# 26-TouchPad4P.net
KiCad netlist of a schematic drawn in Altium Designer
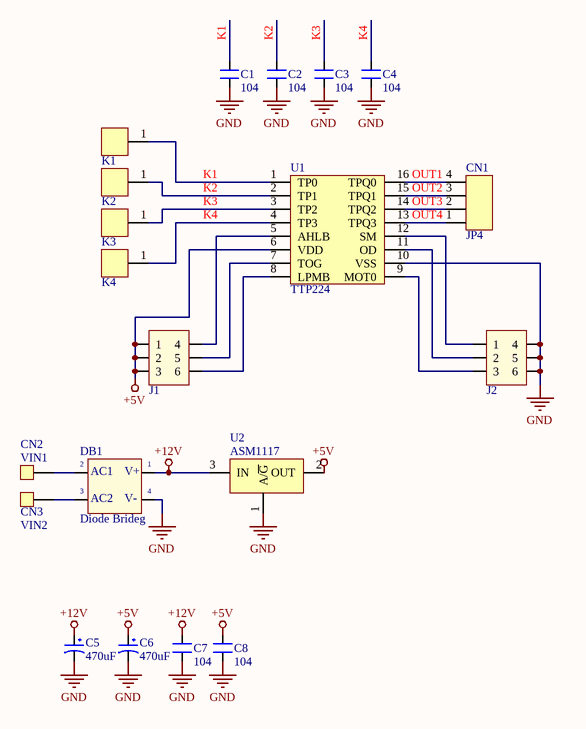
[diagram p0: 26-TouchPad4P.SchDoc]

(export (version "E")
  (design (tool "Eeschema 10.0.6"))
  (components
    (comp (ref "C1")
      (value "104")
      (footprint "C-0805")
      (fields (field (name "DESIGNED BY") "VanDungEvn"))
      (libsource (lib "syhaunguyen") (part "CN"))
    )
    (comp (ref "C2")
      (value "104")
      (footprint "C-0805")
      (fields (field (name "DESIGNED BY") "VanDungEvn"))
      (libsource (lib "syhaunguyen") (part "CN"))
    )
    (comp (ref "C3")
      (value "104")
      (footprint "C-0805")
      (fields (field (name "DESIGNED BY") "VanDungEvn"))
      (libsource (lib "syhaunguyen") (part "CN"))
    )
    (comp (ref "C4")
      (value "104")
      (footprint "C-0805")
      (fields (field (name "DESIGNED BY") "VanDungEvn"))
      (libsource (lib "syhaunguyen") (part "CN"))
    )
    (comp (ref "C5")
      (value "470uF")
      (footprint "C-ALU-D6.5")
      (description "Cap P  0,1uF < 22uF , 16 - 50V")
      (libsource (lib "PART") (part "CP1"))
    )
    (comp (ref "C6")
      (value "470uF")
      (footprint "C-ALU-D6.5")
      (description "Cap P  0,1uF < 22uF , 16 - 50V")
      (libsource (lib "PART") (part "CP1"))
    )
    (comp (ref "C7")
      (value "104")
      (footprint "C-0805")
      (fields (field (name "DESIGNED BY") "VanDungEvn"))
      (libsource (lib "syhaunguyen") (part "CN"))
    )
    (comp (ref "C8")
      (value "104")
      (footprint "C-0805")
      (fields (field (name "DESIGNED BY") "VanDungEvn"))
      (libsource (lib "syhaunguyen") (part "CN"))
    )
    (comp (ref "CN1") (value "JP4") (footprint "JP4") (libsource (lib "doAnTotNghiep2017Lib") (part "JP4")))
    (comp (ref "CN2")
      (value "VIN1")
      (footprint "M3")
      (libsource (lib "doAnTotNghiep2017Lib") (part "COCDONGM3"))
    )
    (comp (ref "CN3")
      (value "VIN2")
      (footprint "M3")
      (libsource (lib "doAnTotNghiep2017Lib") (part "COCDONGM3"))
    )
    (comp (ref "DB1")
      (value "Diode Brideg")
      (footprint "D-DB-1A-SMD")
      (description "Convert AC to DC voltage, 4 pin")
      (libsource (lib "PART") (part "DB"))
    )
    (comp (ref "J1")
      (value "Connector 3x2")
      (footprint "JP3x2")
      (libsource (lib "syhaunguyen") (part "JP3x2"))
    )
    (comp (ref "J2")
      (value "Connector 3x2")
      (footprint "JP3x2")
      (libsource (lib "syhaunguyen") (part "JP3x2"))
    )
    (comp (ref "K1") (value "SWCP") (footprint "SWCP") (libsource (lib "doAnTotNghiep2017Lib") (part "SWCP")))
    (comp (ref "K2") (value "SWCP") (footprint "SWCP") (libsource (lib "doAnTotNghiep2017Lib") (part "SWCP")))
    (comp (ref "K3") (value "SWCP") (footprint "SWCP") (libsource (lib "doAnTotNghiep2017Lib") (part "SWCP")))
    (comp (ref "K4") (value "SWCP") (footprint "SWCP") (libsource (lib "doAnTotNghiep2017Lib") (part "SWCP")))
    (comp (ref "U1")
      (value "TTP224")
      (footprint "SSOP-20")
      (libsource (lib "doAnTotNghiep2017Lib") (part "TTP224"))
    )
    (comp (ref "U2")
      (value "ASM1117")
      (footprint "TO-252")
      (libsource (lib "doAnTotNghiep2017Lib") (part "ASM1117"))
    )
  )
  (nets
    (net (code "1") (name "+5V") (class "Default")
      (node (ref "C6") (pin "1") (pinfunction "1_1") (pintype "passive"))
      (node (ref "C8") (pin "2") (pinfunction "2_2") (pintype "passive"))
      (node (ref "J1") (pin "1") (pinfunction "1_1") (pintype "passive"))
      (node (ref "J1") (pin "2") (pinfunction "2_2") (pintype "passive"))
      (node (ref "J1") (pin "3") (pinfunction "3_3") (pintype "passive"))
      (node (ref "U1") (pin "6") (pinfunction "VDD_6") (pintype "passive"))
      (node (ref "U2") (pin "2") (pinfunction "OUT_2") (pintype "passive"))
    )
    (net (code "2") (name "+12V") (class "Default")
      (node (ref "C5") (pin "1") (pinfunction "1_1") (pintype "passive"))
      (node (ref "C7") (pin "2") (pinfunction "2_2") (pintype "passive"))
      (node (ref "DB1") (pin "3") (pinfunction "AC2_3") (pintype "passive"))
      (node (ref "U2") (pin "3") (pinfunction "IN_3") (pintype "passive"))
    )
    (net (code "3") (name "/K1") (class "Default")
      (node (ref "C1") (pin "2") (pinfunction "2_2") (pintype "passive"))
      (node (ref "K1") (pin "1") (pintype "passive"))
      (node (ref "U1") (pin "1") (pinfunction "TP0_1") (pintype "passive"))
    )
    (net (code "4") (name "/K2") (class "Default")
      (node (ref "C2") (pin "2") (pinfunction "2_2") (pintype "passive"))
      (node (ref "K2") (pin "1") (pintype "passive"))
      (node (ref "U1") (pin "2") (pinfunction "TP1_2") (pintype "passive"))
    )
    (net (code "5") (name "/K3") (class "Default")
      (node (ref "C3") (pin "2") (pinfunction "2_2") (pintype "passive"))
      (node (ref "K3") (pin "1") (pintype "passive"))
      (node (ref "U1") (pin "3") (pinfunction "TP2_3") (pintype "passive"))
    )
    (net (code "6") (name "/K4") (class "Default")
      (node (ref "C4") (pin "2") (pinfunction "2_2") (pintype "passive"))
      (node (ref "K4") (pin "1") (pintype "passive"))
      (node (ref "U1") (pin "4") (pinfunction "TP3_4") (pintype "passive"))
    )
    (net (code "7") (name "/OUT1") (class "Default")
      (node (ref "CN1") (pin "4") (pintype "passive"))
      (node (ref "U1") (pin "16") (pinfunction "TPQ0_16") (pintype "passive"))
    )
    (net (code "8") (name "/OUT2") (class "Default")
      (node (ref "CN1") (pin "3") (pintype "passive"))
      (node (ref "U1") (pin "15") (pinfunction "TPQ1_15") (pintype "passive"))
    )
    (net (code "9") (name "/OUT3") (class "Default")
      (node (ref "CN1") (pin "2") (pintype "passive"))
      (node (ref "U1") (pin "14") (pinfunction "TPQ2_14") (pintype "passive"))
    )
    (net (code "10") (name "/OUT4") (class "Default")
      (node (ref "CN1") (pin "1") (pintype "passive"))
      (node (ref "U1") (pin "13") (pinfunction "TPQ3_13") (pintype "passive"))
    )
    (net (code "11") (name "GND") (class "Default")
      (node (ref "C1") (pin "1") (pinfunction "1_1") (pintype "passive"))
      (node (ref "C2") (pin "1") (pinfunction "1_1") (pintype "passive"))
      (node (ref "C3") (pin "1") (pinfunction "1_1") (pintype "passive"))
      (node (ref "C4") (pin "1") (pinfunction "1_1") (pintype "passive"))
      (node (ref "C5") (pin "2") (pinfunction "2_2") (pintype "passive"))
      (node (ref "C6") (pin "2") (pinfunction "2_2") (pintype "passive"))
      (node (ref "C7") (pin "1") (pinfunction "1_1") (pintype "passive"))
      (node (ref "C8") (pin "1") (pinfunction "1_1") (pintype "passive"))
      (node (ref "DB1") (pin "4") (pinfunction "-V_OUT_4") (pintype "passive"))
      (node (ref "J2") (pin "4") (pinfunction "4_4") (pintype "passive"))
      (node (ref "J2") (pin "5") (pinfunction "5_5") (pintype "passive"))
      (node (ref "J2") (pin "6") (pinfunction "6_6") (pintype "passive"))
      (node (ref "U1") (pin "10") (pinfunction "VSS_10") (pintype "passive"))
      (node (ref "U2") (pin "1") (pinfunction "A/~{G}_1") (pintype "passive"))
    )
    (net (code "12") (name "Net-(DB1-+V_OUT)") (class "Default")
      (node (ref "CN3") (pin "1") (pintype "passive"))
      (node (ref "DB1") (pin "1") (pinfunction "+V_OUT_1") (pintype "passive"))
    )
    (net (code "13") (name "Net-(DB1-AC1)") (class "Default")
      (node (ref "CN2") (pin "1") (pintype "passive"))
      (node (ref "DB1") (pin "2") (pinfunction "AC1_2") (pintype "passive"))
    )
    (net (code "14") (name "Net-(U1-AHLB)") (class "Default")
      (node (ref "J1") (pin "4") (pinfunction "4_4") (pintype "passive"))
      (node (ref "U1") (pin "5") (pinfunction "AHLB_5") (pintype "passive"))
    )
    (net (code "15") (name "Net-(U1-LPMB)") (class "Default")
      (node (ref "J1") (pin "6") (pinfunction "6_6") (pintype "passive"))
      (node (ref "U1") (pin "8") (pinfunction "LPMB_8") (pintype "passive"))
    )
    (net (code "16") (name "Net-(U1-MOT0)") (class "Default")
      (node (ref "J2") (pin "3") (pinfunction "3_3") (pintype "passive"))
      (node (ref "U1") (pin "9") (pinfunction "MOT0_9") (pintype "passive"))
    )
    (net (code "17") (name "Net-(U1-OD)") (class "Default")
      (node (ref "J2") (pin "2") (pinfunction "2_2") (pintype "passive"))
      (node (ref "U1") (pin "11") (pinfunction "OD_11") (pintype "passive"))
    )
    (net (code "18") (name "Net-(U1-SM)") (class "Default")
      (node (ref "J2") (pin "1") (pinfunction "1_1") (pintype "passive"))
      (node (ref "U1") (pin "12") (pinfunction "SM_12") (pintype "passive"))
    )
    (net (code "19") (name "Net-(U1-TOG)") (class "Default")
      (node (ref "J1") (pin "5") (pinfunction "5_5") (pintype "passive"))
      (node (ref "U1") (pin "7") (pinfunction "TOG_7") (pintype "passive"))
    )
  )
)
